# EDCPSUr9v0.net
KiCad netlist of a schematic drawn in EAGLE
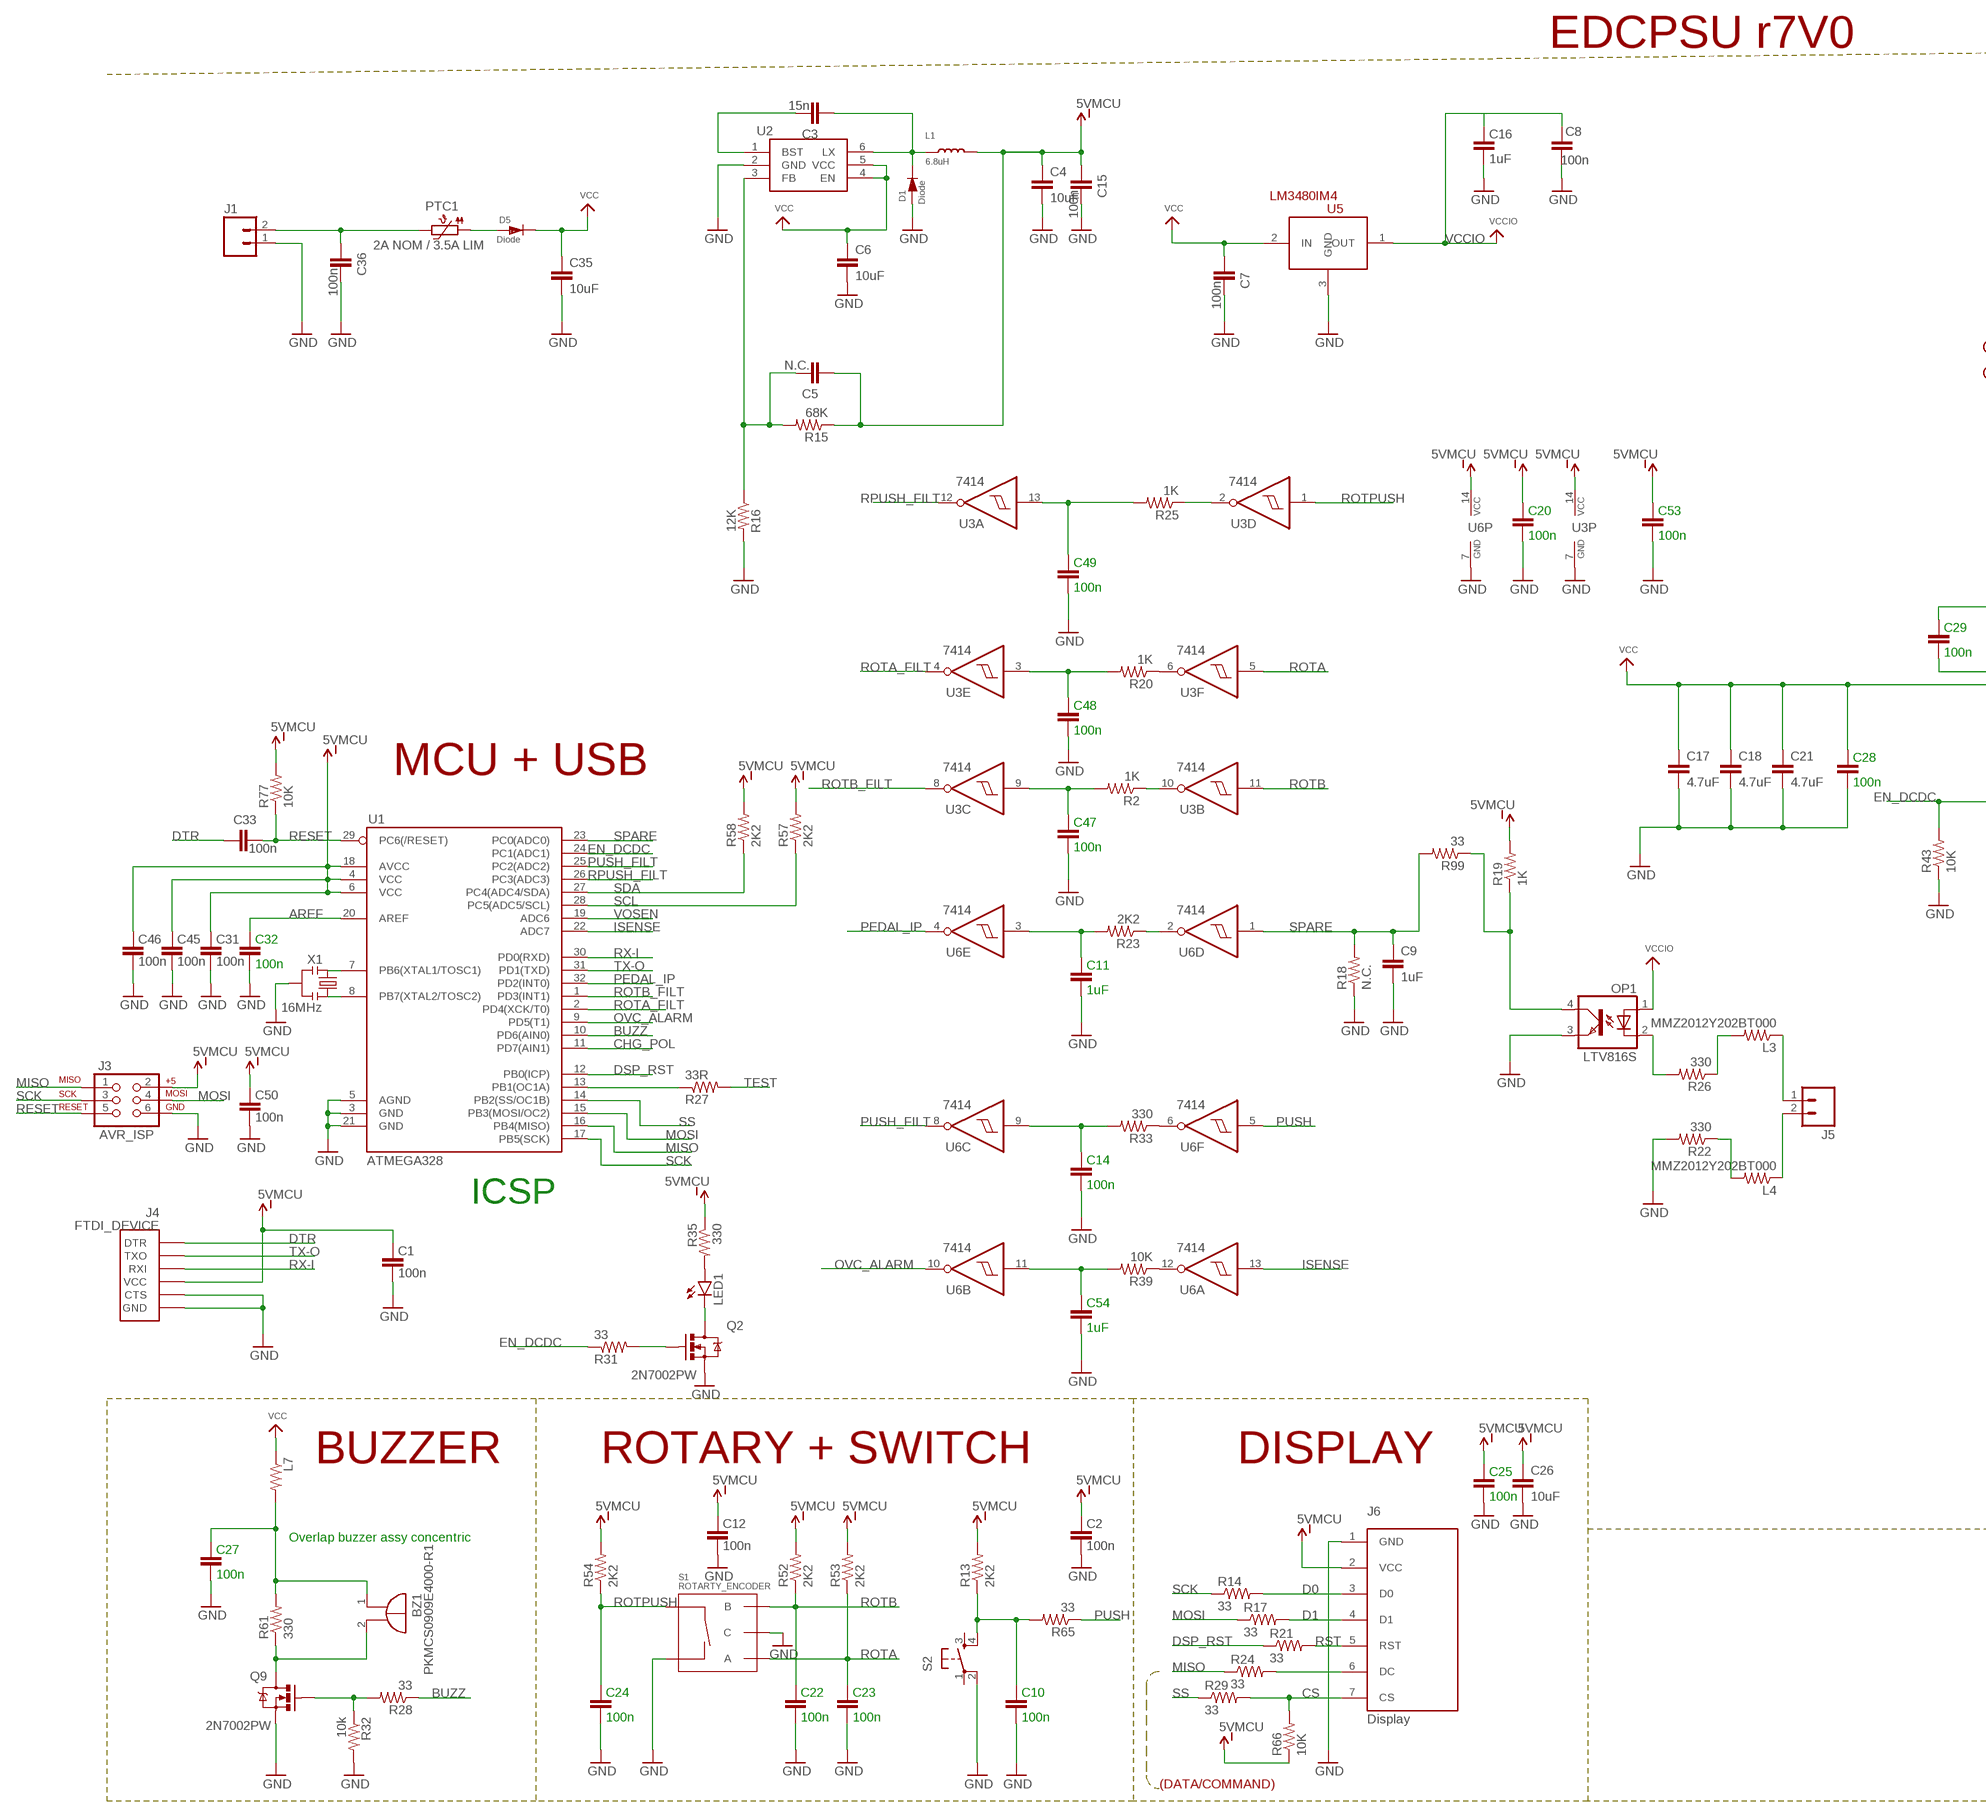
[diagram p0: schematic, sheet 1, part 1 of 2]
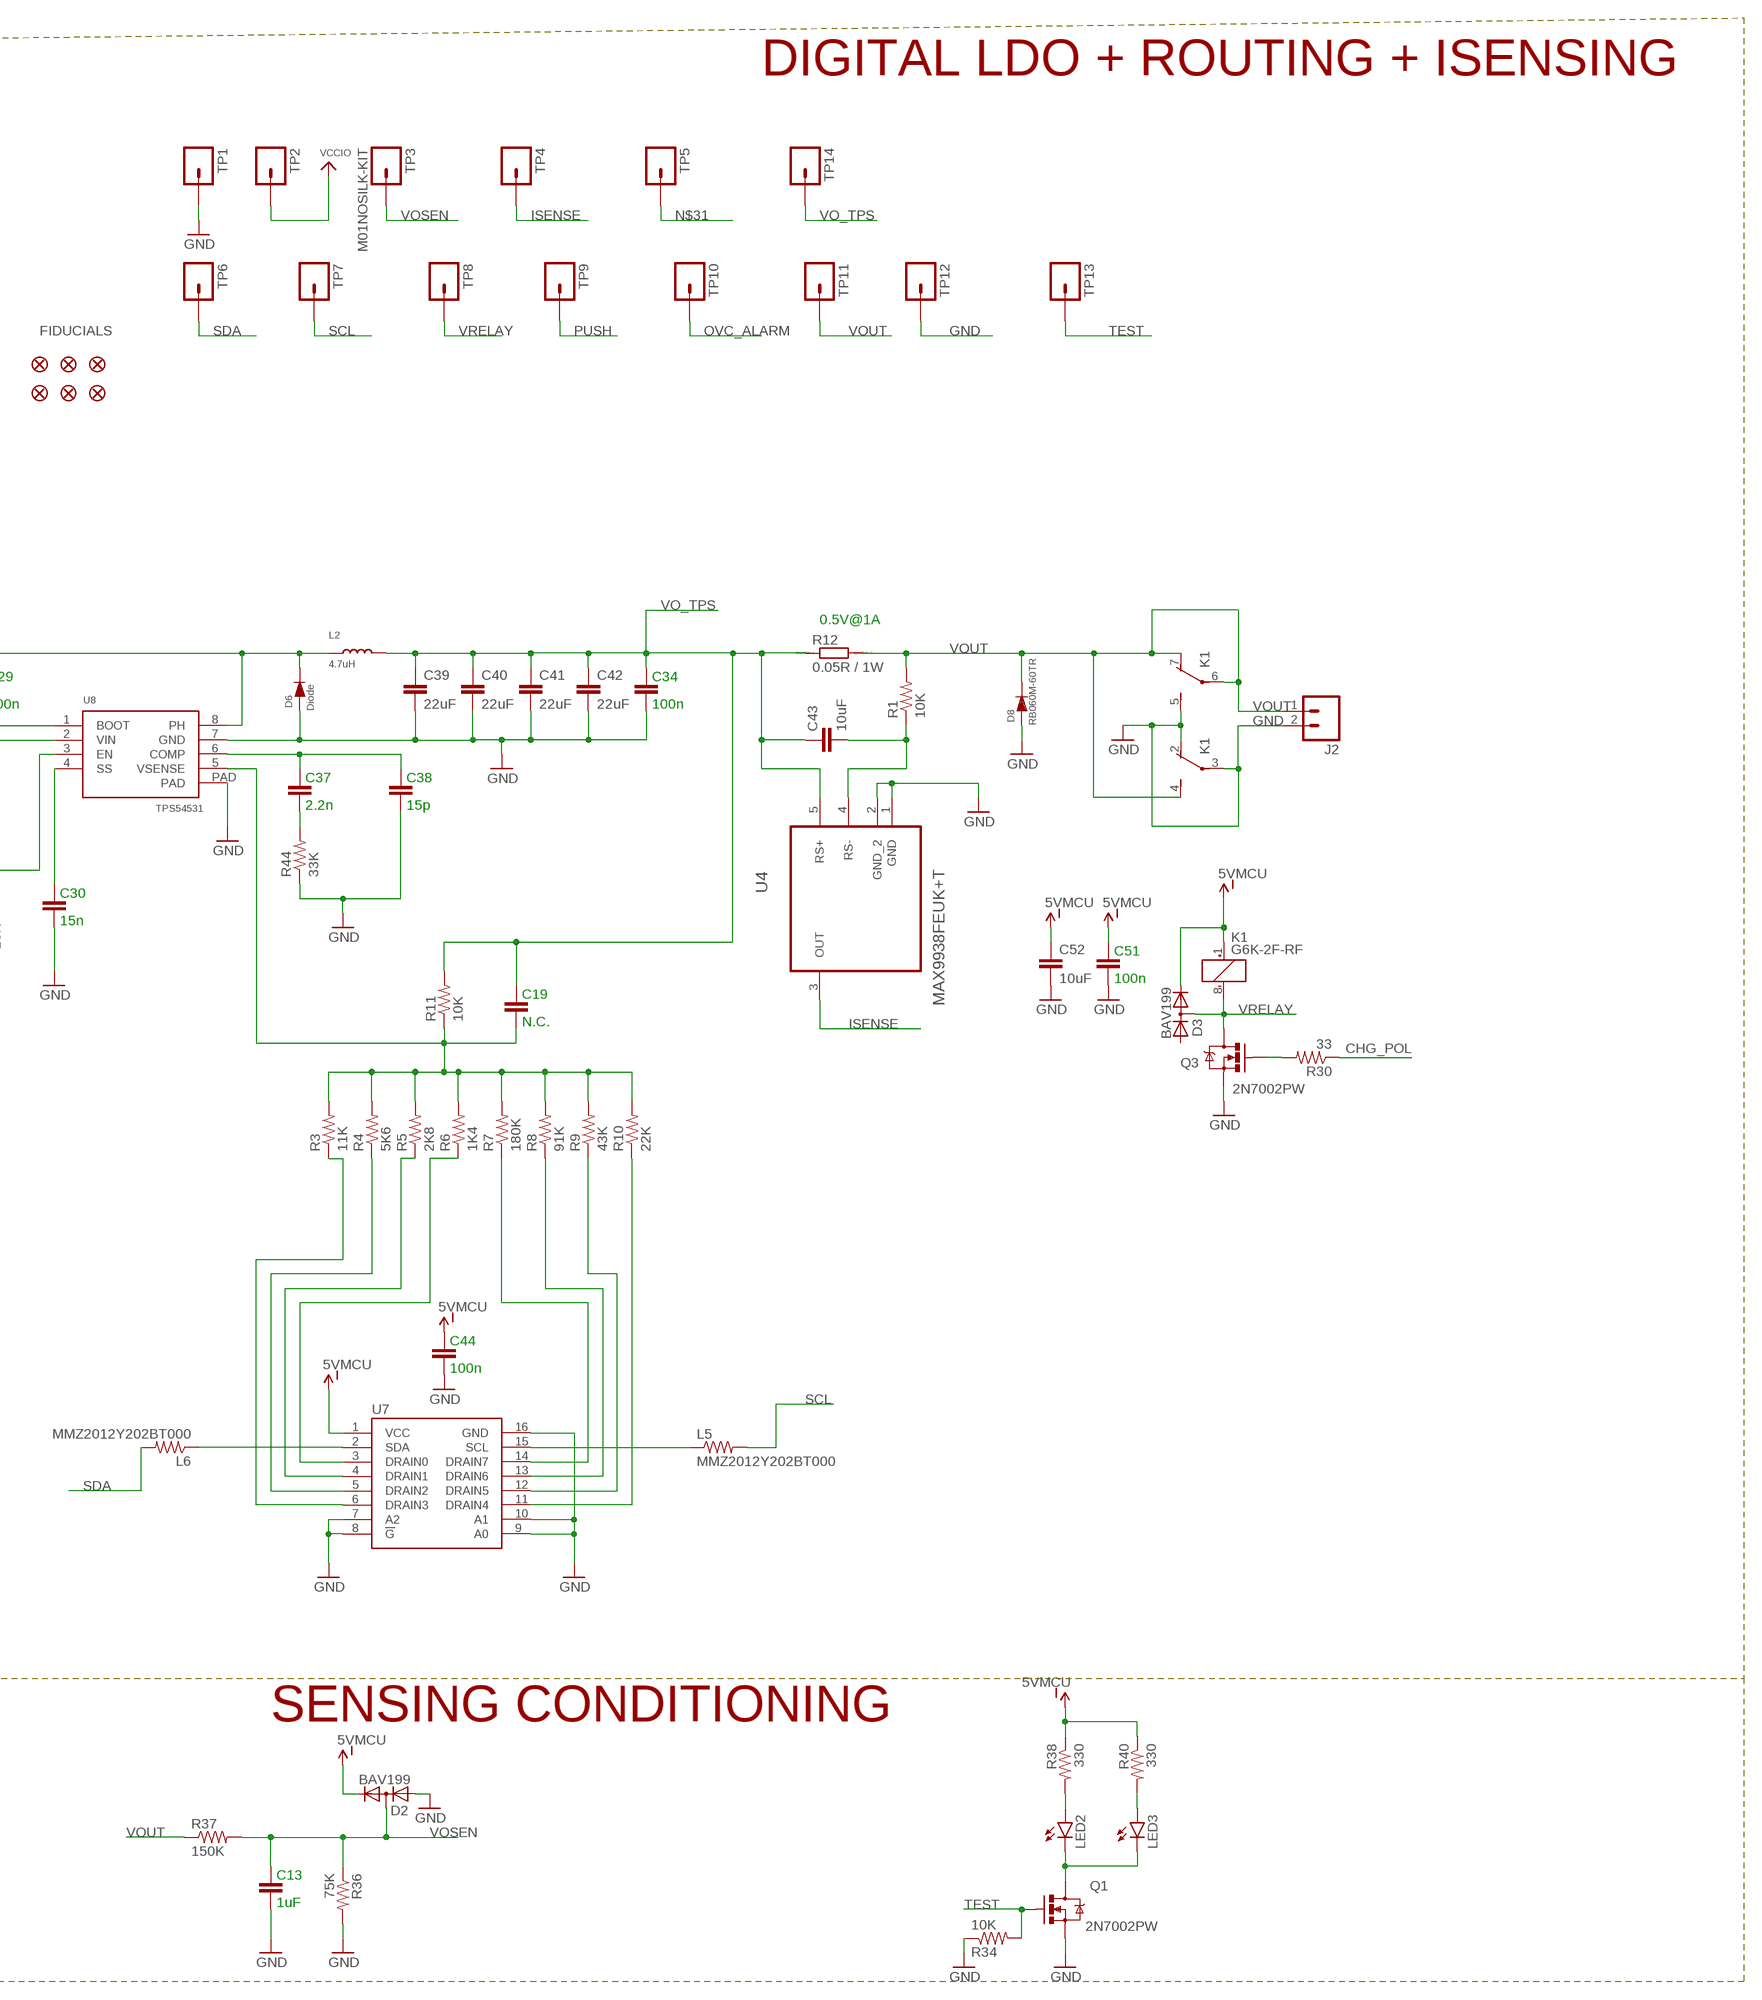
[diagram p1: schematic, sheet 1, part 2 of 2]

(export (version "E")
  (design (tool "Eeschema 10.0.6"))
  (components
    (comp (ref "BZ1")
      (value "PKMCS0909E4000-R1")
      (footprint "eagle-import:PKMCS0909")
      (libsource (lib "eagle-import") (part "PKMCS0909E4000-R1"))
    )
    (comp (ref "C1")
      (value "100n")
      (footprint "eagle-import:0805")
      (libsource (lib "eagle-import") (part "CAP0805"))
    )
    (comp (ref "C2")
      (value "100n")
      (footprint "eagle-import:0805")
      (libsource (lib "eagle-import") (part "CAP0805"))
    )
    (comp (ref "C3")
      (value "15n")
      (footprint "eagle-import:0805")
      (libsource (lib "eagle-import") (part "CAP0805"))
    )
    (comp (ref "C4")
      (value "10uF")
      (footprint "eagle-import:1206")
      (libsource (lib "eagle-import") (part "SparkFun-Passives_CAP1206"))
    )
    (comp (ref "C5")
      (value "N.C.")
      (footprint "eagle-import:0805")
      (libsource (lib "eagle-import") (part "CAP0805"))
    )
    (comp (ref "C6")
      (value "10uF")
      (footprint "eagle-import:1206")
      (libsource (lib "eagle-import") (part "SparkFun-Passives_CAP1206"))
    )
    (comp (ref "C7")
      (value "100n")
      (footprint "eagle-import:0805")
      (libsource (lib "eagle-import") (part "CAP0805"))
    )
    (comp (ref "C8")
      (value "100n")
      (footprint "eagle-import:0805")
      (libsource (lib "eagle-import") (part "CAP0805"))
    )
    (comp (ref "C9")
      (value "1uF")
      (footprint "eagle-import:1206")
      (libsource (lib "eagle-import") (part "SparkFun-Passives_CAP1206"))
    )
    (comp (ref "C10")
      (value "100n")
      (footprint "eagle-import:0805")
      (libsource (lib "eagle-import") (part "CAP0805"))
    )
    (comp (ref "C11")
      (value "1uF")
      (footprint "eagle-import:0805")
      (libsource (lib "eagle-import") (part "CAP0805"))
    )
    (comp (ref "C12")
      (value "100n")
      (footprint "eagle-import:0805")
      (libsource (lib "eagle-import") (part "CAP0805"))
    )
    (comp (ref "C13")
      (value "1uF")
      (footprint "eagle-import:0805")
      (libsource (lib "eagle-import") (part "CAP0805"))
    )
    (comp (ref "C14")
      (value "100n")
      (footprint "eagle-import:0805")
      (libsource (lib "eagle-import") (part "CAP0805"))
    )
    (comp (ref "C15")
      (value "100n")
      (footprint "eagle-import:0805")
      (libsource (lib "eagle-import") (part "CAP0805"))
    )
    (comp (ref "C16")
      (value "1uF")
      (footprint "eagle-import:0805")
      (libsource (lib "eagle-import") (part "CAP0805"))
    )
    (comp (ref "C17")
      (value "4.7uF")
      (footprint "eagle-import:1210")
      (libsource (lib "eagle-import") (part "SparkFun-Passives_CAP1210"))
    )
    (comp (ref "C18")
      (value "4.7uF")
      (footprint "eagle-import:1210")
      (libsource (lib "eagle-import") (part "SparkFun-Passives_CAP1210"))
    )
    (comp (ref "C19")
      (value "N.C.")
      (footprint "eagle-import:0805")
      (libsource (lib "eagle-import") (part "CAP0805"))
    )
    (comp (ref "C20")
      (value "100n")
      (footprint "eagle-import:0805")
      (libsource (lib "eagle-import") (part "CAP0805"))
    )
    (comp (ref "C21")
      (value "4.7uF")
      (footprint "eagle-import:1210")
      (libsource (lib "eagle-import") (part "SparkFun-Passives_CAP1210"))
    )
    (comp (ref "C22")
      (value "100n")
      (footprint "eagle-import:0805")
      (libsource (lib "eagle-import") (part "CAP0805"))
    )
    (comp (ref "C23")
      (value "100n")
      (footprint "eagle-import:0805")
      (libsource (lib "eagle-import") (part "CAP0805"))
    )
    (comp (ref "C24")
      (value "100n")
      (footprint "eagle-import:0805")
      (libsource (lib "eagle-import") (part "CAP0805"))
    )
    (comp (ref "C25")
      (value "100n")
      (footprint "eagle-import:0805")
      (libsource (lib "eagle-import") (part "CAP0805"))
    )
    (comp (ref "C26")
      (value "10uF")
      (footprint "eagle-import:1206")
      (libsource (lib "eagle-import") (part "SparkFun-Passives_CAP1206"))
    )
    (comp (ref "C27")
      (value "100n")
      (footprint "eagle-import:0805")
      (libsource (lib "eagle-import") (part "CAP0805"))
    )
    (comp (ref "C28")
      (value "100n")
      (footprint "eagle-import:0805")
      (libsource (lib "eagle-import") (part "CAP0805"))
    )
    (comp (ref "C29")
      (value "100n")
      (footprint "eagle-import:0805")
      (libsource (lib "eagle-import") (part "CAP0805"))
    )
    (comp (ref "C30")
      (value "15n")
      (footprint "eagle-import:0805")
      (libsource (lib "eagle-import") (part "CAP0805"))
    )
    (comp (ref "C31")
      (value "100n")
      (footprint "eagle-import:0805")
      (libsource (lib "eagle-import") (part "CAP0805"))
    )
    (comp (ref "C32")
      (value "100n")
      (footprint "eagle-import:0805")
      (libsource (lib "eagle-import") (part "CAP0805"))
    )
    (comp (ref "C33")
      (value "100n")
      (footprint "eagle-import:0805")
      (libsource (lib "eagle-import") (part "CAP0805"))
    )
    (comp (ref "C34")
      (value "100n")
      (footprint "eagle-import:0805")
      (libsource (lib "eagle-import") (part "CAP0805"))
    )
    (comp (ref "C35")
      (value "10uF")
      (footprint "eagle-import:1206")
      (libsource (lib "eagle-import") (part "SparkFun-Passives_CAP1206"))
    )
    (comp (ref "C36")
      (value "100n")
      (footprint "eagle-import:0805")
      (libsource (lib "eagle-import") (part "CAP0805"))
    )
    (comp (ref "C37")
      (value "2.2n")
      (footprint "eagle-import:0805")
      (libsource (lib "eagle-import") (part "CAP0805"))
    )
    (comp (ref "C38")
      (value "15p")
      (footprint "eagle-import:0805")
      (libsource (lib "eagle-import") (part "CAP0805"))
    )
    (comp (ref "C39")
      (value "22uF")
      (footprint "eagle-import:1210")
      (libsource (lib "eagle-import") (part "SparkFun-Passives_CAP1210"))
    )
    (comp (ref "C40")
      (value "22uF")
      (footprint "eagle-import:1210")
      (libsource (lib "eagle-import") (part "SparkFun-Passives_CAP1210"))
    )
    (comp (ref "C41")
      (value "22uF")
      (footprint "eagle-import:1210")
      (libsource (lib "eagle-import") (part "SparkFun-Passives_CAP1210"))
    )
    (comp (ref "C42")
      (value "22uF")
      (footprint "eagle-import:1210")
      (libsource (lib "eagle-import") (part "SparkFun-Passives_CAP1210"))
    )
    (comp (ref "C43")
      (value "10uF")
      (footprint "eagle-import:1206")
      (libsource (lib "eagle-import") (part "SparkFun-Passives_CAP1206"))
    )
    (comp (ref "C44")
      (value "100n")
      (footprint "eagle-import:0805")
      (libsource (lib "eagle-import") (part "CAP0805"))
    )
    (comp (ref "C45")
      (value "100n")
      (footprint "eagle-import:0805")
      (libsource (lib "eagle-import") (part "CAP0805"))
    )
    (comp (ref "C46")
      (value "100n")
      (footprint "eagle-import:0805")
      (libsource (lib "eagle-import") (part "CAP0805"))
    )
    (comp (ref "C47")
      (value "100n")
      (footprint "eagle-import:0805")
      (libsource (lib "eagle-import") (part "CAP0805"))
    )
    (comp (ref "C48")
      (value "100n")
      (footprint "eagle-import:0805")
      (libsource (lib "eagle-import") (part "CAP0805"))
    )
    (comp (ref "C49")
      (value "100n")
      (footprint "eagle-import:0805")
      (libsource (lib "eagle-import") (part "CAP0805"))
    )
    (comp (ref "C50")
      (value "100n")
      (footprint "eagle-import:0805")
      (libsource (lib "eagle-import") (part "CAP0805"))
    )
    (comp (ref "C51")
      (value "100n")
      (footprint "eagle-import:0805")
      (libsource (lib "eagle-import") (part "CAP0805"))
    )
    (comp (ref "C52")
      (value "10uF")
      (footprint "eagle-import:1206")
      (libsource (lib "eagle-import") (part "SparkFun-Passives_CAP1206"))
    )
    (comp (ref "C53")
      (value "100n")
      (footprint "eagle-import:0805")
      (libsource (lib "eagle-import") (part "CAP0805"))
    )
    (comp (ref "C54")
      (value "1uF")
      (footprint "eagle-import:0805")
      (libsource (lib "eagle-import") (part "CAP0805"))
    )
    (comp (ref "D1")
      (value "Diode")
      (footprint "eagle-import:SOD123")
      (libsource (lib "eagle-import") (part "DSOD123"))
    )
    (comp (ref "D2")
      (value "BAV199")
      (footprint "eagle-import:SOT23")
      (libsource (lib "eagle-import") (part "BAV199"))
    )
    (comp (ref "D3")
      (value "BAV199")
      (footprint "eagle-import:SOT23")
      (libsource (lib "eagle-import") (part "BAV199"))
    )
    (comp (ref "D5")
      (value "Diode")
      (footprint "eagle-import:DO-214AB")
      (libsource (lib "eagle-import") (part "DSMC"))
    )
    (comp (ref "D6")
      (value "Diode")
      (footprint "eagle-import:DO-214AB")
      (libsource (lib "eagle-import") (part "DSMC"))
    )
    (comp (ref "D8")
      (value "RB060M-60TR")
      (footprint "eagle-import:SMADIODE")
      (libsource (lib "eagle-import") (part "DSMA"))
    )
    (comp (ref "FID1")
      (value "FIDUCIAL1X2")
      (footprint "eagle-import:FIDUCIAL-1X2")
      (libsource (lib "eagle-import") (part "FIDUCIAL1X2"))
    )
    (comp (ref "FID2")
      (value "FIDUCIAL1X2")
      (footprint "eagle-import:FIDUCIAL-1X2")
      (libsource (lib "eagle-import") (part "FIDUCIAL1X2"))
    )
    (comp (ref "FID3")
      (value "FIDUCIAL1X2")
      (footprint "eagle-import:FIDUCIAL-1X2")
      (libsource (lib "eagle-import") (part "FIDUCIAL1X2"))
    )
    (comp (ref "FID4")
      (value "FIDUCIAL1X2")
      (footprint "eagle-import:FIDUCIAL-1X2")
      (libsource (lib "eagle-import") (part "FIDUCIAL1X2"))
    )
    (comp (ref "FID5")
      (value "FIDUCIAL1X2")
      (footprint "eagle-import:FIDUCIAL-1X2")
      (libsource (lib "eagle-import") (part "FIDUCIAL1X2"))
    )
    (comp (ref "FID6")
      (value "FIDUCIAL1X2")
      (footprint "eagle-import:FIDUCIAL-1X2")
      (libsource (lib "eagle-import") (part "FIDUCIAL1X2"))
    )
    (comp (ref "J1")
      (value "M02LOCK_LONGPADS")
      (footprint "eagle-import:1X02_LOCK_LONGPADS")
      (libsource (lib "eagle-import") (part "M02LOCK_LONGPADS"))
    )
    (comp (ref "J2")
      (value "M02LOCK_LONGPADS")
      (footprint "eagle-import:1X02_LOCK_LONGPADS")
      (libsource (lib "eagle-import") (part "M02LOCK_LONGPADS"))
    )
    (comp (ref "J3")
      (value "AVR_ISP")
      (footprint "eagle-import:2X3")
      (libsource (lib "eagle-import") (part "AVR_SPI_PRG_6PTH"))
    )
    (comp (ref "J4")
      (value "FTDI_DEVICE")
      (footprint "eagle-import:FTDI_DEVICE_SIDE")
      (libsource (lib "eagle-import") (part "FTDI_DEVICE"))
    )
    (comp (ref "J5")
      (value "M02LOCK_LONGPADS")
      (footprint "eagle-import:1X02_LOCK_LONGPADS")
      (libsource (lib "eagle-import") (part "M02LOCK_LONGPADS"))
    )
    (comp (ref "J6")
      (value "Display")
      (footprint "eagle-import:OLED_LCD")
      (libsource (lib "eagle-import") (part "OLED_LCD"))
    )
    (comp (ref "K1")
      (value "G6K-2F-RF")
      (footprint "eagle-import:G6K-RF")
      (fields (field (name "MF") "OMRON COMPONENTS USA") (field (name "MPN") "G6K-2F-RF-DC12"))
      (libsource (lib "eagle-import") (part "G6K-2F-RF"))
    )
    (comp (ref "L1")
      (value "6.8uH")
      (footprint "eagle-import:NR4018T100M")
      (libsource (lib "eagle-import") (part "L4018"))
    )
    (comp (ref "L2")
      (value "4.7uH")
      (footprint "eagle-import:WE-LHMI")
      (libsource (lib "eagle-import") (part "L74437368047"))
    )
    (comp (ref "L3")
      (value "MMZ2012Y202BT000")
      (footprint "eagle-import:0805")
      (libsource (lib "eagle-import") (part "RESISTOR0805-RES"))
    )
    (comp (ref "L4")
      (value "MMZ2012Y202BT000")
      (footprint "eagle-import:0805")
      (libsource (lib "eagle-import") (part "RESISTOR0805-RES"))
    )
    (comp (ref "L5")
      (value "MMZ2012Y202BT000")
      (footprint "eagle-import:0805")
      (libsource (lib "eagle-import") (part "RESISTOR0805-RES"))
    )
    (comp (ref "L6")
      (value "MMZ2012Y202BT000")
      (footprint "eagle-import:0805")
      (libsource (lib "eagle-import") (part "RESISTOR0805-RES"))
    )
    (comp (ref "L7")
      (value "MMZ2012Y202BT000")
      (footprint "eagle-import:0805")
      (libsource (lib "eagle-import") (part "RESISTOR0805-RES"))
    )
    (comp (ref "LED1")
      (value "LED3MM")
      (footprint "eagle-import:LED3MM")
      (libsource (lib "eagle-import") (part "LED3MM"))
    )
    (comp (ref "LED2")
      (value "LED5MM")
      (footprint "eagle-import:LED5MM")
      (libsource (lib "eagle-import") (part "LED5MM"))
    )
    (comp (ref "LED3")
      (value "LED5MM")
      (footprint "eagle-import:LED5MM")
      (libsource (lib "eagle-import") (part "LED5MM"))
    )
    (comp (ref "OP1")
      (value "LTV816S")
      (footprint "eagle-import:SMD4")
      (libsource (lib "eagle-import") (part "LTV816S"))
    )
    (comp (ref "PTC1")
      (value "2A NOM / 3.5A LIM")
      (footprint "eagle-import:1812L")
      (libsource (lib "eagle-import") (part "PTC-"))
    )
    (comp (ref "Q1")
      (value "2N7002PW")
      (footprint "eagle-import:SOT323")
      (libsource (lib "eagle-import") (part "MOSFET-NCHANNEL2N7002PW"))
    )
    (comp (ref "Q2")
      (value "2N7002PW")
      (footprint "eagle-import:SOT323")
      (libsource (lib "eagle-import") (part "MOSFET-NCHANNEL2N7002PW"))
    )
    (comp (ref "Q3")
      (value "2N7002PW")
      (footprint "eagle-import:SOT323")
      (libsource (lib "eagle-import") (part "MOSFET-NCHANNEL2N7002PW"))
    )
    (comp (ref "Q9")
      (value "2N7002PW")
      (footprint "eagle-import:SOT323")
      (libsource (lib "eagle-import") (part "MOSFET-NCHANNEL2N7002PW"))
    )
    (comp (ref "R1")
      (value "10K")
      (footprint "eagle-import:0805")
      (libsource (lib "eagle-import") (part "RESISTOR0805-RES"))
    )
    (comp (ref "R2")
      (value "1K")
      (footprint "eagle-import:0805")
      (libsource (lib "eagle-import") (part "RESISTOR0805-RES"))
    )
    (comp (ref "R3")
      (value "11K")
      (footprint "eagle-import:0805")
      (libsource (lib "eagle-import") (part "RESISTOR0805-RES"))
    )
    (comp (ref "R4")
      (value "5K6")
      (footprint "eagle-import:0805")
      (libsource (lib "eagle-import") (part "RESISTOR0805-RES"))
    )
    (comp (ref "R5")
      (value "2K8")
      (footprint "eagle-import:0805")
      (libsource (lib "eagle-import") (part "RESISTOR0805-RES"))
    )
    (comp (ref "R6")
      (value "1K4")
      (footprint "eagle-import:0805")
      (libsource (lib "eagle-import") (part "RESISTOR0805-RES"))
    )
    (comp (ref "R7")
      (value "180K")
      (footprint "eagle-import:0805")
      (libsource (lib "eagle-import") (part "RESISTOR0805-RES"))
    )
    (comp (ref "R8")
      (value "91K")
      (footprint "eagle-import:0805")
      (libsource (lib "eagle-import") (part "RESISTOR0805-RES"))
    )
    (comp (ref "R9")
      (value "43K")
      (footprint "eagle-import:0805")
      (libsource (lib "eagle-import") (part "RESISTOR0805-RES"))
    )
    (comp (ref "R10")
      (value "22K")
      (footprint "eagle-import:0805")
      (libsource (lib "eagle-import") (part "RESISTOR0805-RES"))
    )
    (comp (ref "R11")
      (value "10K")
      (footprint "eagle-import:0805")
      (libsource (lib "eagle-import") (part "RESISTOR0805-RES"))
    )
    (comp (ref "R12")
      (value "0.05R / 1W")
      (footprint "eagle-import:R2512")
      (libsource (lib "eagle-import") (part "RR2512"))
    )
    (comp (ref "R13")
      (value "2K2")
      (footprint "eagle-import:0805")
      (libsource (lib "eagle-import") (part "RESISTOR0805-RES"))
    )
    (comp (ref "R14")
      (value "33")
      (footprint "eagle-import:0805")
      (libsource (lib "eagle-import") (part "RESISTOR0805-RES"))
    )
    (comp (ref "R15")
      (value "68K")
      (footprint "eagle-import:0805")
      (libsource (lib "eagle-import") (part "RESISTOR0805-RES"))
    )
    (comp (ref "R16")
      (value "12K")
      (footprint "eagle-import:0805")
      (libsource (lib "eagle-import") (part "RESISTOR0805-RES"))
    )
    (comp (ref "R17")
      (value "33")
      (footprint "eagle-import:0805")
      (libsource (lib "eagle-import") (part "RESISTOR0805-RES"))
    )
    (comp (ref "R18")
      (value "N.C.")
      (footprint "eagle-import:0805")
      (libsource (lib "eagle-import") (part "RESISTOR0805-RES"))
    )
    (comp (ref "R19")
      (value "1K")
      (footprint "eagle-import:0805")
      (libsource (lib "eagle-import") (part "RESISTOR0805-RES"))
    )
    (comp (ref "R20")
      (value "1K")
      (footprint "eagle-import:0805")
      (libsource (lib "eagle-import") (part "RESISTOR0805-RES"))
    )
    (comp (ref "R21")
      (value "33")
      (footprint "eagle-import:0805")
      (libsource (lib "eagle-import") (part "RESISTOR0805-RES"))
    )
    (comp (ref "R22")
      (value "330")
      (footprint "eagle-import:1206")
      (libsource (lib "eagle-import") (part "SparkFun-Passives_RESISTOR1206"))
    )
    (comp (ref "R23")
      (value "2K2")
      (footprint "eagle-import:0805")
      (libsource (lib "eagle-import") (part "RESISTOR0805-RES"))
    )
    (comp (ref "R24")
      (value "33")
      (footprint "eagle-import:0805")
      (libsource (lib "eagle-import") (part "RESISTOR0805-RES"))
    )
    (comp (ref "R25")
      (value "1K")
      (footprint "eagle-import:0805")
      (libsource (lib "eagle-import") (part "RESISTOR0805-RES"))
    )
    (comp (ref "R26")
      (value "330")
      (footprint "eagle-import:1206")
      (libsource (lib "eagle-import") (part "SparkFun-Passives_RESISTOR1206"))
    )
    (comp (ref "R27")
      (value "33R")
      (footprint "eagle-import:0805")
      (libsource (lib "eagle-import") (part "RESISTOR0805-RES"))
    )
    (comp (ref "R28")
      (value "33")
      (footprint "eagle-import:0805")
      (libsource (lib "eagle-import") (part "RESISTOR0805-RES"))
    )
    (comp (ref "R29")
      (value "33")
      (footprint "eagle-import:0805")
      (libsource (lib "eagle-import") (part "RESISTOR0805-RES"))
    )
    (comp (ref "R30")
      (value "33")
      (footprint "eagle-import:0805")
      (libsource (lib "eagle-import") (part "RESISTOR0805-RES"))
    )
    (comp (ref "R31")
      (value "33")
      (footprint "eagle-import:0805")
      (libsource (lib "eagle-import") (part "RESISTOR0805-RES"))
    )
    (comp (ref "R32")
      (value "10k")
      (footprint "eagle-import:0805")
      (libsource (lib "eagle-import") (part "RESISTOR0805-RES"))
    )
    (comp (ref "R33")
      (value "330")
      (footprint "eagle-import:0805")
      (libsource (lib "eagle-import") (part "RESISTOR0805-RES"))
    )
    (comp (ref "R34")
      (value "10K")
      (footprint "eagle-import:0805")
      (libsource (lib "eagle-import") (part "RESISTOR0805-RES"))
    )
    (comp (ref "R35")
      (value "330")
      (footprint "eagle-import:0805")
      (libsource (lib "eagle-import") (part "RESISTOR0805-RES"))
    )
    (comp (ref "R36")
      (value "75K")
      (footprint "eagle-import:0805")
      (libsource (lib "eagle-import") (part "RESISTOR0805-RES"))
    )
    (comp (ref "R37")
      (value "150K")
      (footprint "eagle-import:0805")
      (libsource (lib "eagle-import") (part "RESISTOR0805-RES"))
    )
    (comp (ref "R38")
      (value "330")
      (footprint "eagle-import:0805")
      (libsource (lib "eagle-import") (part "RESISTOR0805-RES"))
    )
    (comp (ref "R39")
      (value "10K")
      (footprint "eagle-import:0805")
      (libsource (lib "eagle-import") (part "RESISTOR0805-RES"))
    )
    (comp (ref "R40")
      (value "330")
      (footprint "eagle-import:0805")
      (libsource (lib "eagle-import") (part "RESISTOR0805-RES"))
    )
    (comp (ref "R43")
      (value "10K")
      (footprint "eagle-import:0805")
      (libsource (lib "eagle-import") (part "RESISTOR0805-RES"))
    )
    (comp (ref "R44")
      (value "33K")
      (footprint "eagle-import:0805")
      (libsource (lib "eagle-import") (part "RESISTOR0805-RES"))
    )
    (comp (ref "R52")
      (value "2K2")
      (footprint "eagle-import:0805")
      (libsource (lib "eagle-import") (part "RESISTOR0805-RES"))
    )
    (comp (ref "R53")
      (value "2K2")
      (footprint "eagle-import:0805")
      (libsource (lib "eagle-import") (part "RESISTOR0805-RES"))
    )
    (comp (ref "R54")
      (value "2K2")
      (footprint "eagle-import:0805")
      (libsource (lib "eagle-import") (part "RESISTOR0805-RES"))
    )
    (comp (ref "R57")
      (value "2K2")
      (footprint "eagle-import:0805")
      (libsource (lib "eagle-import") (part "RESISTOR0805-RES"))
    )
    (comp (ref "R58")
      (value "2K2")
      (footprint "eagle-import:0805")
      (libsource (lib "eagle-import") (part "RESISTOR0805-RES"))
    )
    (comp (ref "R61")
      (value "330")
      (footprint "eagle-import:0805")
      (libsource (lib "eagle-import") (part "RESISTOR0805-RES"))
    )
    (comp (ref "R65")
      (value "33")
      (footprint "eagle-import:0805")
      (libsource (lib "eagle-import") (part "RESISTOR0805-RES"))
    )
    (comp (ref "R66")
      (value "10K")
      (footprint "eagle-import:0805")
      (libsource (lib "eagle-import") (part "RESISTOR0805-RES"))
    )
    (comp (ref "R77")
      (value "10K")
      (footprint "eagle-import:0805")
      (libsource (lib "eagle-import") (part "RESISTOR0805-RES"))
    )
    (comp (ref "R99")
      (value "33")
      (footprint "eagle-import:0805")
      (libsource (lib "eagle-import") (part "RESISTOR0805-RES"))
    )
    (comp (ref "S1")
      (value "ROTARTY_ENCODER")
      (footprint "eagle-import:ROTARY_ENC_PLAIN")
      (libsource (lib "eagle-import") (part "ROTARTY_ENCODER"))
    )
    (comp (ref "S2")
      (value "TAC_SWITCH_KSC931G-SMD")
      (footprint "eagle-import:TAC_SW_SMD_KSC931G")
      (libsource (lib "eagle-import") (part "TAC_SWITCH_KSC931G-SMD"))
    )
    (comp (ref "TP1")
      (value "M01POGOPIN_HOLE_LARGE")
      (footprint "eagle-import:1X01_POGOPIN_HOLE_LARGE")
      (libsource (lib "eagle-import") (part "M01POGOPIN_HOLE_LARGE"))
    )
    (comp (ref "TP2")
      (value "M01POGOPIN_HOLE_LARGE")
      (footprint "eagle-import:1X01_POGOPIN_HOLE_LARGE")
      (libsource (lib "eagle-import") (part "M01POGOPIN_HOLE_LARGE"))
    )
    (comp (ref "TP3")
      (value "M01NOSILK-KIT")
      (footprint "eagle-import:1X01NS-KIT")
      (libsource (lib "eagle-import") (part "M01NOSILK-KIT"))
    )
    (comp (ref "TP4")
      (value "M01POGOPIN_HOLE_LARGE")
      (footprint "eagle-import:1X01_POGOPIN_HOLE_LARGE")
      (libsource (lib "eagle-import") (part "M01POGOPIN_HOLE_LARGE"))
    )
    (comp (ref "TP5")
      (value "M01POGOPIN_HOLE_LARGE")
      (footprint "eagle-import:1X01_POGOPIN_HOLE_LARGE")
      (libsource (lib "eagle-import") (part "M01POGOPIN_HOLE_LARGE"))
    )
    (comp (ref "TP6")
      (value "M01POGOPIN_HOLE_LARGE")
      (footprint "eagle-import:1X01_POGOPIN_HOLE_LARGE")
      (libsource (lib "eagle-import") (part "M01POGOPIN_HOLE_LARGE"))
    )
    (comp (ref "TP7")
      (value "M01POGOPIN_HOLE_LARGE")
      (footprint "eagle-import:1X01_POGOPIN_HOLE_LARGE")
      (libsource (lib "eagle-import") (part "M01POGOPIN_HOLE_LARGE"))
    )
    (comp (ref "TP8")
      (value "M01POGOPIN_HOLE_LARGE")
      (footprint "eagle-import:1X01_POGOPIN_HOLE_LARGE")
      (libsource (lib "eagle-import") (part "M01POGOPIN_HOLE_LARGE"))
    )
    (comp (ref "TP9")
      (value "M01POGOPIN_HOLE_LARGE")
      (footprint "eagle-import:1X01_POGOPIN_HOLE_LARGE")
      (libsource (lib "eagle-import") (part "M01POGOPIN_HOLE_LARGE"))
    )
    (comp (ref "TP10")
      (value "M01POGOPIN_HOLE_LARGE")
      (footprint "eagle-import:1X01_POGOPIN_HOLE_LARGE")
      (libsource (lib "eagle-import") (part "M01POGOPIN_HOLE_LARGE"))
    )
    (comp (ref "TP11")
      (value "M01POGOPIN_HOLE_LARGE")
      (footprint "eagle-import:1X01_POGOPIN_HOLE_LARGE")
      (libsource (lib "eagle-import") (part "M01POGOPIN_HOLE_LARGE"))
    )
    (comp (ref "TP12")
      (value "M01POGOPIN_HOLE_LARGE")
      (footprint "eagle-import:1X01_POGOPIN_HOLE_LARGE")
      (libsource (lib "eagle-import") (part "M01POGOPIN_HOLE_LARGE"))
    )
    (comp (ref "TP13")
      (value "M01POGOPIN_HOLE_LARGE")
      (footprint "eagle-import:1X01_POGOPIN_HOLE_LARGE")
      (libsource (lib "eagle-import") (part "M01POGOPIN_HOLE_LARGE"))
    )
    (comp (ref "TP14")
      (value "M01POGOPIN_HOLE_LARGE")
      (footprint "eagle-import:1X01_POGOPIN_HOLE_LARGE")
      (libsource (lib "eagle-import") (part "M01POGOPIN_HOLE_LARGE"))
    )
    (comp (ref "U1")
      (value "ATMEGA328")
      (footprint "eagle-import:TQFP32-08")
      (libsource (lib "eagle-import") (part "ATMEGA168"))
    )
    (comp (ref "U2")
      (value "BD9G101G")
      (footprint "eagle-import:SSOP6")
      (libsource (lib "eagle-import") (part "BD9G101G"))
    )
    (comp (ref "U3")
      (value "7414")
      (footprint "eagle-import:TSSOP14")
      (libsource (lib "eagle-import") (part "7414"))
    )
    (comp (ref "U4")
      (value "MAX9938FEUK+T")
      (footprint "eagle-import:SOT95P280X145-5N")
      (libsource (lib "eagle-import") (part "MAX9938FEUK+T"))
    )
    (comp (ref "U5")
      (value "LM3480IM4")
      (footprint "eagle-import:SOT23-3")
      (libsource (lib "eagle-import") (part "LM3480IM4"))
    )
    (comp (ref "U6")
      (value "7414")
      (footprint "eagle-import:TSSOP14")
      (libsource (lib "eagle-import") (part "7414"))
    )
    (comp (ref "U7")
      (value "TPIC2810D")
      (footprint "eagle-import:SO16")
      (libsource (lib "eagle-import") (part "TPIC2810D"))
    )
    (comp (ref "U8")
      (value "TPS54531")
      (footprint "eagle-import:SOIC8")
      (libsource (lib "eagle-import") (part "TPS5431DDAR"))
    )
    (comp (ref "X1")
      (value "16MHz")
      (footprint "eagle-import:RESONATOR-SMD")
      (libsource (lib "eagle-import") (part "RESONATORSMD"))
    )
  )
  (nets
    (net (code "1") (name "/AREF") (class "Default")
      (node (ref "C32") (pin "2") (pinfunction "2_2") (pintype "passive"))
      (node (ref "U1") (pin "20") (pinfunction "AREF_20") (pintype "bidirectional"))
    )
    (net (code "2") (name "/BUZZ") (class "Default")
      (node (ref "R28") (pin "1") (pinfunction "1_1") (pintype "passive"))
      (node (ref "U1") (pin "10") (pinfunction "PD6(AIN0)_10") (pintype "bidirectional"))
    )
    (net (code "3") (name "/CHG_POL") (class "Default")
      (node (ref "R30") (pin "1") (pinfunction "1_1") (pintype "passive"))
      (node (ref "U1") (pin "11") (pinfunction "PD7(AIN1)_11") (pintype "bidirectional"))
    )
    (net (code "4") (name "/CS") (class "Default")
      (node (ref "J6") (pin "7") (pinfunction "CS_7") (pintype "bidirectional"))
      (node (ref "R29") (pin "2") (pinfunction "2_2") (pintype "passive"))
      (node (ref "R66") (pin "2") (pinfunction "2_2") (pintype "passive"))
    )
    (net (code "5") (name "/D0") (class "Default")
      (node (ref "J6") (pin "3") (pinfunction "D0_3") (pintype "bidirectional"))
      (node (ref "R14") (pin "2") (pinfunction "2_2") (pintype "passive"))
    )
    (net (code "6") (name "/D1") (class "Default")
      (node (ref "J6") (pin "4") (pinfunction "D1_4") (pintype "bidirectional"))
      (node (ref "R17") (pin "2") (pinfunction "2_2") (pintype "passive"))
    )
    (net (code "7") (name "/DSP_RST") (class "Default")
      (node (ref "R21") (pin "1") (pinfunction "1_1") (pintype "passive"))
      (node (ref "U1") (pin "12") (pinfunction "PB0(ICP)_12") (pintype "bidirectional"))
    )
    (net (code "8") (name "/DTR") (class "Default")
      (node (ref "C33") (pin "2") (pinfunction "2_2") (pintype "passive"))
      (node (ref "J4") (pin "P$1") (pinfunction "DTR_P$1") (pintype "bidirectional"))
    )
    (net (code "9") (name "/EN_DCDC") (class "Default")
      (node (ref "R31") (pin "1") (pinfunction "1_1") (pintype "passive"))
      (node (ref "R43") (pin "2") (pinfunction "2_2") (pintype "passive"))
      (node (ref "U1") (pin "24") (pinfunction "PC1(ADC1)_24") (pintype "bidirectional"))
      (node (ref "U8") (pin "3") (pinfunction "EN_3") (pintype "bidirectional"))
    )
    (net (code "10") (name "/ISENSE") (class "Default")
      (node (ref "TP4") (pin "1") (pinfunction "1_1") (pintype "passive"))
      (node (ref "U1") (pin "22") (pinfunction "ADC7_22") (pintype "bidirectional"))
      (node (ref "U4") (pin "3") (pinfunction "OUT_3") (pintype "output"))
      (node (ref "U6") (pin "13") (pinfunction "I_13") (pintype "input"))
    )
    (net (code "11") (name "/MISO") (class "Default")
      (node (ref "J3") (pin "1") (pinfunction "1_1") (pintype "passive"))
      (node (ref "R24") (pin "1") (pinfunction "1_1") (pintype "passive"))
      (node (ref "U1") (pin "16") (pinfunction "PB4(MISO)_16") (pintype "bidirectional"))
    )
    (net (code "12") (name "/MOSI") (class "Default")
      (node (ref "J3") (pin "4") (pinfunction "4_4") (pintype "passive"))
      (node (ref "R17") (pin "1") (pinfunction "1_1") (pintype "passive"))
      (node (ref "U1") (pin "15") (pinfunction "PB3(MOSI/OC2)_15") (pintype "bidirectional"))
    )
    (net (code "13") (name "/N$31") (class "Default")
      (node (ref "OP1") (pin "4") (pinfunction "COL_4") (pintype "passive"))
      (node (ref "R19") (pin "1") (pinfunction "1_1") (pintype "passive"))
      (node (ref "R99") (pin "1") (pinfunction "1_1") (pintype "passive"))
      (node (ref "TP5") (pin "1") (pinfunction "1_1") (pintype "passive"))
    )
    (net (code "14") (name "/OVC_ALARM") (class "Default")
      (node (ref "TP10") (pin "1") (pinfunction "1_1") (pintype "passive"))
      (node (ref "U1") (pin "9") (pinfunction "PD5(T1)_9") (pintype "bidirectional"))
      (node (ref "U6") (pin "10") (pinfunction "O_10") (pintype "output"))
    )
    (net (code "15") (name "/PEDAL_IP") (class "Default")
      (node (ref "U1") (pin "32") (pinfunction "PD2(INT0)_32") (pintype "bidirectional"))
      (node (ref "U6") (pin "4") (pinfunction "O_4") (pintype "output"))
    )
    (net (code "16") (name "/PUSH") (class "Default")
      (node (ref "R65") (pin "1") (pinfunction "1_1") (pintype "passive"))
      (node (ref "TP9") (pin "1") (pinfunction "1_1") (pintype "passive"))
      (node (ref "U6") (pin "5") (pinfunction "I_5") (pintype "input"))
    )
    (net (code "17") (name "/PUSH_FILT") (class "Default")
      (node (ref "U1") (pin "25") (pinfunction "PC2(ADC2)_25") (pintype "bidirectional"))
      (node (ref "U6") (pin "8") (pinfunction "O_8") (pintype "output"))
    )
    (net (code "18") (name "/RESET") (class "Default")
      (node (ref "C33") (pin "1") (pinfunction "1_1") (pintype "passive"))
      (node (ref "J3") (pin "5") (pinfunction "5_5") (pintype "passive"))
      (node (ref "R77") (pin "1") (pinfunction "1_1") (pintype "passive"))
      (node (ref "U1") (pin "29") (pinfunction "PC6(/RESET)_29") (pintype "bidirectional"))
    )
    (net (code "19") (name "/ROTA") (class "Default")
      (node (ref "C23") (pin "2") (pinfunction "2_2") (pintype "passive"))
      (node (ref "R53") (pin "1") (pinfunction "1_1") (pintype "passive"))
      (node (ref "S1") (pin "A") (pinfunction "A_A") (pintype "bidirectional"))
      (node (ref "U3") (pin "5") (pinfunction "I_5") (pintype "input"))
    )
    (net (code "20") (name "/ROTA_FILT") (class "Default")
      (node (ref "U1") (pin "2") (pinfunction "PD4(XCK/T0)_2") (pintype "bidirectional"))
      (node (ref "U3") (pin "4") (pinfunction "O_4") (pintype "output"))
    )
    (net (code "21") (name "/ROTB") (class "Default")
      (node (ref "C22") (pin "2") (pinfunction "2_2") (pintype "passive"))
      (node (ref "R52") (pin "1") (pinfunction "1_1") (pintype "passive"))
      (node (ref "S1") (pin "B") (pinfunction "B_B") (pintype "bidirectional"))
      (node (ref "U3") (pin "11") (pinfunction "I_11") (pintype "input"))
    )
    (net (code "22") (name "/ROTB_FILT") (class "Default")
      (node (ref "U1") (pin "1") (pinfunction "PD3(INT1)_1") (pintype "bidirectional"))
      (node (ref "U3") (pin "8") (pinfunction "O_8") (pintype "output"))
    )
    (net (code "23") (name "/ROTPUSH") (class "Default")
      (node (ref "C24") (pin "2") (pinfunction "2_2") (pintype "passive"))
      (node (ref "R54") (pin "1") (pinfunction "1_1") (pintype "passive"))
      (node (ref "S1") (pin "SW+") (pinfunction "SW+_SW+") (pintype "bidirectional"))
      (node (ref "U3") (pin "1") (pinfunction "I_1") (pintype "input"))
    )
    (net (code "24") (name "/RPUSH_FILT") (class "Default")
      (node (ref "U1") (pin "26") (pinfunction "PC3(ADC3)_26") (pintype "bidirectional"))
      (node (ref "U3") (pin "12") (pinfunction "O_12") (pintype "output"))
    )
    (net (code "25") (name "/RST") (class "Default")
      (node (ref "J6") (pin "5") (pinfunction "RST_5") (pintype "bidirectional"))
      (node (ref "R21") (pin "2") (pinfunction "2_2") (pintype "passive"))
    )
    (net (code "26") (name "/RX-I") (class "Default")
      (node (ref "J4") (pin "P$3") (pinfunction "RXI_P$3") (pintype "bidirectional"))
      (node (ref "U1") (pin "30") (pinfunction "PD0(RXD)_30") (pintype "bidirectional"))
    )
    (net (code "27") (name "/SCK") (class "Default")
      (node (ref "J3") (pin "3") (pinfunction "3_3") (pintype "passive"))
      (node (ref "R14") (pin "1") (pinfunction "1_1") (pintype "passive"))
      (node (ref "U1") (pin "17") (pinfunction "PB5(SCK)_17") (pintype "bidirectional"))
    )
    (net (code "28") (name "/SCL") (class "Default")
      (node (ref "L5") (pin "2") (pinfunction "2_2") (pintype "passive"))
      (node (ref "R57") (pin "1") (pinfunction "1_1") (pintype "passive"))
      (node (ref "TP7") (pin "1") (pinfunction "1_1") (pintype "passive"))
      (node (ref "U1") (pin "28") (pinfunction "PC5(ADC5/SCL)_28") (pintype "bidirectional"))
    )
    (net (code "29") (name "/SDA") (class "Default")
      (node (ref "L6") (pin "2") (pinfunction "2_2") (pintype "passive"))
      (node (ref "R58") (pin "1") (pinfunction "1_1") (pintype "passive"))
      (node (ref "TP6") (pin "1") (pinfunction "1_1") (pintype "passive"))
      (node (ref "U1") (pin "27") (pinfunction "PC4(ADC4/SDA)_27") (pintype "bidirectional"))
    )
    (net (code "30") (name "/SPARE") (class "Default")
      (node (ref "C9") (pin "1") (pinfunction "1_1") (pintype "passive"))
      (node (ref "R18") (pin "2") (pinfunction "2_2") (pintype "passive"))
      (node (ref "R99") (pin "2") (pinfunction "2_2") (pintype "passive"))
      (node (ref "U1") (pin "23") (pinfunction "PC0(ADC0)_23") (pintype "bidirectional"))
      (node (ref "U6") (pin "1") (pinfunction "I_1") (pintype "input"))
    )
    (net (code "31") (name "/SS") (class "Default")
      (node (ref "R29") (pin "1") (pinfunction "1_1") (pintype "passive"))
      (node (ref "U1") (pin "14") (pinfunction "PB2(SS/OC1B)_14") (pintype "bidirectional"))
    )
    (net (code "32") (name "/TEST") (class "Default")
      (node (ref "Q1") (pin "1") (pinfunction "G_1") (pintype "passive"))
      (node (ref "R27") (pin "2") (pinfunction "2_2") (pintype "passive"))
      (node (ref "R34") (pin "2") (pinfunction "2_2") (pintype "passive"))
      (node (ref "TP13") (pin "1") (pinfunction "1_1") (pintype "passive"))
    )
    (net (code "33") (name "/TX-O") (class "Default")
      (node (ref "J4") (pin "P$2") (pinfunction "TXO_P$2") (pintype "bidirectional"))
      (node (ref "U1") (pin "31") (pinfunction "PD1(TXD)_31") (pintype "bidirectional"))
    )
    (net (code "34") (name "/VOSEN") (class "Default")
      (node (ref "C13") (pin "2") (pinfunction "2_2") (pintype "passive"))
      (node (ref "D2") (pin "3") (pinfunction "AC_3") (pintype "passive"))
      (node (ref "R36") (pin "1") (pinfunction "1_1") (pintype "passive"))
      (node (ref "R37") (pin "2") (pinfunction "2_2") (pintype "passive"))
      (node (ref "TP3") (pin "1") (pinfunction "1_1") (pintype "passive"))
      (node (ref "U1") (pin "19") (pinfunction "ADC6_19") (pintype "bidirectional"))
    )
    (net (code "35") (name "/VOUT") (class "Default")
      (node (ref "D8") (pin "C") (pinfunction "K_C") (pintype "bidirectional"))
      (node (ref "J2") (pin "1") (pinfunction "1_1") (pintype "passive"))
      (node (ref "K1") (pin "4") (pinfunction "S_4") (pintype "passive"))
      (node (ref "K1") (pin "6") (pinfunction "P_6") (pintype "passive"))
      (node (ref "K1") (pin "7") (pinfunction "O_7") (pintype "passive"))
      (node (ref "R1") (pin "2") (pinfunction "2_2") (pintype "passive"))
      (node (ref "R12") (pin "2") (pinfunction "2_2") (pintype "passive"))
      (node (ref "R37") (pin "1") (pinfunction "1_1") (pintype "passive"))
      (node (ref "TP11") (pin "1") (pinfunction "1_1") (pintype "passive"))
    )
    (net (code "36") (name "/VO_TPS") (class "Default")
      (node (ref "C19") (pin "2") (pinfunction "2_2") (pintype "passive"))
      (node (ref "C34") (pin "2") (pinfunction "2_2") (pintype "passive"))
      (node (ref "C39") (pin "1") (pinfunction "1_1") (pintype "passive"))
      (node (ref "C40") (pin "1") (pinfunction "1_1") (pintype "passive"))
      (node (ref "C41") (pin "1") (pinfunction "1_1") (pintype "passive"))
      (node (ref "C42") (pin "1") (pinfunction "1_1") (pintype "passive"))
      (node (ref "C43") (pin "1") (pinfunction "1_1") (pintype "passive"))
      (node (ref "L2") (pin "2") (pinfunction "2_2") (pintype "passive"))
      (node (ref "R11") (pin "2") (pinfunction "2_2") (pintype "passive"))
      (node (ref "R12") (pin "1") (pinfunction "1_1") (pintype "passive"))
      (node (ref "TP14") (pin "1") (pinfunction "1_1") (pintype "passive"))
      (node (ref "U4") (pin "5") (pinfunction "RS+_5") (pintype "power_in"))
    )
    (net (code "37") (name "/VRELAY") (class "Default")
      (node (ref "D3") (pin "3") (pinfunction "AC_3") (pintype "passive"))
      (node (ref "K1") (pin "8") (pinfunction "-_8") (pintype "passive"))
      (node (ref "Q3") (pin "3") (pinfunction "D_3") (pintype "passive"))
      (node (ref "TP8") (pin "1") (pinfunction "1_1") (pintype "passive"))
    )
    (net (code "38") (name "5VMCU") (class "Default")
      (node (ref "C1") (pin "2") (pinfunction "2_2") (pintype "passive"))
      (node (ref "C12") (pin "2") (pinfunction "2_2") (pintype "passive"))
      (node (ref "C15") (pin "2") (pinfunction "2_2") (pintype "passive"))
      (node (ref "C2") (pin "2") (pinfunction "2_2") (pintype "passive"))
      (node (ref "C20") (pin "2") (pinfunction "2_2") (pintype "passive"))
      (node (ref "C25") (pin "2") (pinfunction "2_2") (pintype "passive"))
      (node (ref "C26") (pin "1") (pinfunction "1_1") (pintype "passive"))
      (node (ref "C31") (pin "2") (pinfunction "2_2") (pintype "passive"))
      (node (ref "C4") (pin "1") (pinfunction "1_1") (pintype "passive"))
      (node (ref "C44") (pin "2") (pinfunction "2_2") (pintype "passive"))
      (node (ref "C45") (pin "2") (pinfunction "2_2") (pintype "passive"))
      (node (ref "C46") (pin "2") (pinfunction "2_2") (pintype "passive"))
      (node (ref "C5") (pin "2") (pinfunction "2_2") (pintype "passive"))
      (node (ref "C50") (pin "2") (pinfunction "2_2") (pintype "passive"))
      (node (ref "C51") (pin "2") (pinfunction "2_2") (pintype "passive"))
      (node (ref "C52") (pin "1") (pinfunction "1_1") (pintype "passive"))
      (node (ref "C53") (pin "2") (pinfunction "2_2") (pintype "passive"))
      (node (ref "D2") (pin "2") (pinfunction "C_2") (pintype "passive"))
      (node (ref "D3") (pin "2") (pinfunction "C_2") (pintype "passive"))
      (node (ref "J3") (pin "2") (pinfunction "2_2") (pintype "passive"))
      (node (ref "J4") (pin "P$4") (pinfunction "VCC_P$4") (pintype "bidirectional"))
      (node (ref "J6") (pin "2") (pinfunction "VCC_2") (pintype "bidirectional"))
      (node (ref "K1") (pin "1") (pinfunction "+_1") (pintype "passive"))
      (node (ref "L1") (pin "2") (pinfunction "2_2") (pintype "passive"))
      (node (ref "R13") (pin "2") (pinfunction "2_2") (pintype "passive"))
      (node (ref "R15") (pin "1") (pinfunction "1_1") (pintype "passive"))
      (node (ref "R19") (pin "2") (pinfunction "2_2") (pintype "passive"))
      (node (ref "R35") (pin "1") (pinfunction "1_1") (pintype "passive"))
      (node (ref "R38") (pin "1") (pinfunction "1_1") (pintype "passive"))
      (node (ref "R40") (pin "1") (pinfunction "1_1") (pintype "passive"))
      (node (ref "R52") (pin "2") (pinfunction "2_2") (pintype "passive"))
      (node (ref "R53") (pin "2") (pinfunction "2_2") (pintype "passive"))
      (node (ref "R54") (pin "2") (pinfunction "2_2") (pintype "passive"))
      (node (ref "R57") (pin "2") (pinfunction "2_2") (pintype "passive"))
      (node (ref "R58") (pin "2") (pinfunction "2_2") (pintype "passive"))
      (node (ref "R66") (pin "1") (pinfunction "1_1") (pintype "passive"))
      (node (ref "R77") (pin "2") (pinfunction "2_2") (pintype "passive"))
      (node (ref "U1") (pin "18") (pinfunction "AVCC_18") (pintype "bidirectional"))
      (node (ref "U1") (pin "4") (pinfunction "VCC_4") (pintype "bidirectional"))
      (node (ref "U1") (pin "6") (pinfunction "VCC_6") (pintype "bidirectional"))
      (node (ref "U3") (pin "14") (pinfunction "VCC_14") (pintype "power_in"))
      (node (ref "U6") (pin "14") (pinfunction "VCC_14") (pintype "power_in"))
      (node (ref "U7") (pin "1") (pinfunction "VCC_1") (pintype "bidirectional"))
    )
    (net (code "39") (name "GND") (class "Default")
      (node (ref "C1") (pin "1") (pinfunction "1_1") (pintype "passive"))
      (node (ref "C10") (pin "1") (pinfunction "1_1") (pintype "passive"))
      (node (ref "C11") (pin "1") (pinfunction "1_1") (pintype "passive"))
      (node (ref "C12") (pin "1") (pinfunction "1_1") (pintype "passive"))
      (node (ref "C13") (pin "1") (pinfunction "1_1") (pintype "passive"))
      (node (ref "C14") (pin "1") (pinfunction "1_1") (pintype "passive"))
      (node (ref "C15") (pin "1") (pinfunction "1_1") (pintype "passive"))
      (node (ref "C16") (pin "1") (pinfunction "1_1") (pintype "passive"))
      (node (ref "C17") (pin "2") (pinfunction "2_2") (pintype "passive"))
      (node (ref "C18") (pin "2") (pinfunction "2_2") (pintype "passive"))
      (node (ref "C2") (pin "1") (pinfunction "1_1") (pintype "passive"))
      (node (ref "C20") (pin "1") (pinfunction "1_1") (pintype "passive"))
      (node (ref "C21") (pin "2") (pinfunction "2_2") (pintype "passive"))
      (node (ref "C22") (pin "1") (pinfunction "1_1") (pintype "passive"))
      (node (ref "C23") (pin "1") (pinfunction "1_1") (pintype "passive"))
      (node (ref "C24") (pin "1") (pinfunction "1_1") (pintype "passive"))
      (node (ref "C25") (pin "1") (pinfunction "1_1") (pintype "passive"))
      (node (ref "C26") (pin "2") (pinfunction "2_2") (pintype "passive"))
      (node (ref "C27") (pin "1") (pinfunction "1_1") (pintype "passive"))
      (node (ref "C28") (pin "1") (pinfunction "1_1") (pintype "passive"))
      (node (ref "C30") (pin "1") (pinfunction "1_1") (pintype "passive"))
      (node (ref "C31") (pin "1") (pinfunction "1_1") (pintype "passive"))
      (node (ref "C32") (pin "1") (pinfunction "1_1") (pintype "passive"))
      (node (ref "C34") (pin "1") (pinfunction "1_1") (pintype "passive"))
      (node (ref "C35") (pin "2") (pinfunction "2_2") (pintype "passive"))
      (node (ref "C36") (pin "1") (pinfunction "1_1") (pintype "passive"))
      (node (ref "C38") (pin "1") (pinfunction "1_1") (pintype "passive"))
      (node (ref "C39") (pin "2") (pinfunction "2_2") (pintype "passive"))
      (node (ref "C4") (pin "2") (pinfunction "2_2") (pintype "passive"))
      (node (ref "C40") (pin "2") (pinfunction "2_2") (pintype "passive"))
      (node (ref "C41") (pin "2") (pinfunction "2_2") (pintype "passive"))
      (node (ref "C42") (pin "2") (pinfunction "2_2") (pintype "passive"))
      (node (ref "C44") (pin "1") (pinfunction "1_1") (pintype "passive"))
      (node (ref "C45") (pin "1") (pinfunction "1_1") (pintype "passive"))
      (node (ref "C46") (pin "1") (pinfunction "1_1") (pintype "passive"))
      (node (ref "C47") (pin "1") (pinfunction "1_1") (pintype "passive"))
      (node (ref "C48") (pin "1") (pinfunction "1_1") (pintype "passive"))
      (node (ref "C49") (pin "1") (pinfunction "1_1") (pintype "passive"))
      (node (ref "C50") (pin "1") (pinfunction "1_1") (pintype "passive"))
      (node (ref "C51") (pin "1") (pinfunction "1_1") (pintype "passive"))
      (node (ref "C52") (pin "2") (pinfunction "2_2") (pintype "passive"))
      (node (ref "C53") (pin "1") (pinfunction "1_1") (pintype "passive"))
      (node (ref "C54") (pin "1") (pinfunction "1_1") (pintype "passive"))
      (node (ref "C6") (pin "2") (pinfunction "2_2") (pintype "passive"))
      (node (ref "C7") (pin "1") (pinfunction "1_1") (pintype "passive"))
      (node (ref "C8") (pin "1") (pinfunction "1_1") (pintype "passive"))
      (node (ref "C9") (pin "2") (pinfunction "2_2") (pintype "passive"))
      (node (ref "D1") (pin "+") (pinfunction "A_+") (pintype "bidirectional"))
      (node (ref "D2") (pin "1") (pinfunction "A_1") (pintype "passive"))
      (node (ref "D6") (pin "1") (pinfunction "A_1") (pintype "bidirectional"))
      (node (ref "D8") (pin "A") (pinfunction "A_A") (pintype "bidirectional"))
      (node (ref "J1") (pin "1") (pinfunction "1_1") (pintype "passive"))
      (node (ref "J2") (pin "2") (pinfunction "2_2") (pintype "passive"))
      (node (ref "J3") (pin "6") (pinfunction "6_6") (pintype "passive"))
      (node (ref "J4") (pin "P$5") (pinfunction "CTS_P$5") (pintype "bidirectional"))
      (node (ref "J4") (pin "P$6") (pinfunction "GND_P$6") (pintype "bidirectional"))
      (node (ref "J6") (pin "1") (pinfunction "GND_1") (pintype "bidirectional"))
      (node (ref "K1") (pin "2") (pinfunction "O_2") (pintype "passive"))
      (node (ref "K1") (pin "3") (pinfunction "P_3") (pintype "passive"))
      (node (ref "K1") (pin "5") (pinfunction "S_5") (pintype "passive"))
      (node (ref "OP1") (pin "3") (pinfunction "EMIT_3") (pintype "passive"))
      (node (ref "Q1") (pin "2") (pinfunction "S_2") (pintype "passive"))
      (node (ref "Q2") (pin "2") (pinfunction "S_2") (pintype "passive"))
      (node (ref "Q3") (pin "2") (pinfunction "S_2") (pintype "passive"))
      (node (ref "Q9") (pin "2") (pinfunction "S_2") (pintype "passive"))
      (node (ref "R16") (pin "2") (pinfunction "2_2") (pintype "passive"))
      (node (ref "R18") (pin "1") (pinfunction "1_1") (pintype "passive"))
      (node (ref "R22") (pin "2") (pinfunction "2_2") (pintype "passive"))
      (node (ref "R32") (pin "2") (pinfunction "2_2") (pintype "passive"))
      (node (ref "R34") (pin "1") (pinfunction "1_1") (pintype "passive"))
      (node (ref "R36") (pin "2") (pinfunction "2_2") (pintype "passive"))
      (node (ref "R43") (pin "1") (pinfunction "1_1") (pintype "passive"))
      (node (ref "R44") (pin "1") (pinfunction "1_1") (pintype "passive"))
      (node (ref "S1") (pin "C") (pinfunction "C_C") (pintype "bidirectional"))
      (node (ref "S1") (pin "SW-") (pinfunction "SW-_SW-") (pintype "bidirectional"))
      (node (ref "S2") (pin "2") (pinfunction "2_2") (pintype "passive"))
      (node (ref "TP1") (pin "1") (pinfunction "1_1") (pintype "passive"))
      (node (ref "TP12") (pin "1") (pinfunction "1_1") (pintype "passive"))
      (node (ref "U1") (pin "21") (pinfunction "GND_21") (pintype "bidirectional"))
      (node (ref "U1") (pin "3") (pinfunction "GND_3") (pintype "bidirectional"))
      (node (ref "U1") (pin "5") (pinfunction "AGND_5") (pintype "bidirectional"))
      (node (ref "U2") (pin "2") (pinfunction "GND_2") (pintype "bidirectional"))
      (node (ref "U3") (pin "7") (pinfunction "GND_7") (pintype "power_in"))
      (node (ref "U4") (pin "1") (pinfunction "GND_1") (pintype "passive"))
      (node (ref "U4") (pin "2") (pinfunction "GND_2_2") (pintype "passive"))
      (node (ref "U5") (pin "3") (pinfunction "GND_3") (pintype "bidirectional"))
      (node (ref "U6") (pin "7") (pinfunction "GND_7") (pintype "power_in"))
      (node (ref "U7") (pin "10") (pinfunction "A1_10") (pintype "bidirectional"))
      (node (ref "U7") (pin "16") (pinfunction "GND_16") (pintype "bidirectional"))
      (node (ref "U7") (pin "7") (pinfunction "A2_7") (pintype "bidirectional"))
      (node (ref "U7") (pin "8") (pinfunction "~{G}_8") (pintype "bidirectional"))
      (node (ref "U7") (pin "9") (pinfunction "A0_9") (pintype "bidirectional"))
      (node (ref "U8") (pin "7") (pinfunction "GND_7") (pintype "bidirectional"))
      (node (ref "U8") (pin "PAD") (pinfunction "PAD_PAD") (pintype "bidirectional"))
      (node (ref "X1") (pin "2") (pinfunction "2_2") (pintype "passive"))
    )
    (net (code "40") (name "Net-(BZ1-+)") (class "Default")
      (node (ref "BZ1") (pin "1") (pinfunction "+_1") (pintype "passive"))
      (node (ref "C27") (pin "2") (pinfunction "2_2") (pintype "passive"))
      (node (ref "L7") (pin "2") (pinfunction "2_2") (pintype "passive"))
      (node (ref "R61") (pin "2") (pinfunction "2_2") (pintype "passive"))
    )
    (net (code "41") (name "Net-(BZ1--)") (class "Default")
      (node (ref "BZ1") (pin "2") (pinfunction "-_2") (pintype "passive"))
      (node (ref "Q9") (pin "3") (pinfunction "D_3") (pintype "passive"))
      (node (ref "R61") (pin "1") (pinfunction "1_1") (pintype "passive"))
    )
    (net (code "42") (name "Net-(C10-Pad2)") (class "Default")
      (node (ref "C10") (pin "2") (pinfunction "2_2") (pintype "passive"))
      (node (ref "R13") (pin "1") (pinfunction "1_1") (pintype "passive"))
      (node (ref "R65") (pin "2") (pinfunction "2_2") (pintype "passive"))
      (node (ref "S2") (pin "4") (pinfunction "4_4") (pintype "passive"))
    )
    (net (code "43") (name "Net-(C36-Pad2)") (class "Default")
      (node (ref "C36") (pin "2") (pinfunction "2_2") (pintype "passive"))
      (node (ref "J1") (pin "2") (pinfunction "2_2") (pintype "passive"))
      (node (ref "PTC1") (pin "2") (pinfunction "2_2") (pintype "passive"))
    )
    (net (code "44") (name "Net-(C37-Pad1)") (class "Default")
      (node (ref "C37") (pin "1") (pinfunction "1_1") (pintype "passive"))
      (node (ref "R44") (pin "2") (pinfunction "2_2") (pintype "passive"))
    )
    (net (code "45") (name "Net-(D1-K)") (class "Default")
      (node (ref "C3") (pin "2") (pinfunction "2_2") (pintype "passive"))
      (node (ref "D1") (pin "-") (pinfunction "K_-") (pintype "bidirectional"))
      (node (ref "L1") (pin "1") (pinfunction "1_1") (pintype "passive"))
      (node (ref "U2") (pin "6") (pinfunction "LX_6") (pintype "bidirectional"))
    )
    (net (code "46") (name "Net-(D5-A)") (class "Default")
      (node (ref "D5") (pin "1") (pinfunction "A_1") (pintype "bidirectional"))
      (node (ref "PTC1") (pin "1") (pinfunction "1_1") (pintype "passive"))
    )
    (net (code "47") (name "Net-(D6-K)") (class "Default")
      (node (ref "C29") (pin "2") (pinfunction "2_2") (pintype "passive"))
      (node (ref "D6") (pin "2") (pinfunction "K_2") (pintype "bidirectional"))
      (node (ref "L2") (pin "1") (pinfunction "1_1") (pintype "passive"))
      (node (ref "U8") (pin "8") (pinfunction "PH_8") (pintype "bidirectional"))
    )
    (net (code "48") (name "Net-(J5-Pad1)") (class "Default")
      (node (ref "J5") (pin "1") (pinfunction "1_1") (pintype "passive"))
      (node (ref "L3") (pin "1") (pinfunction "1_1") (pintype "passive"))
    )
    (net (code "49") (name "Net-(J5-Pad2)") (class "Default")
      (node (ref "J5") (pin "2") (pinfunction "2_2") (pintype "passive"))
      (node (ref "L4") (pin "1") (pinfunction "1_1") (pintype "passive"))
    )
    (net (code "50") (name "Net-(J6-DC)") (class "Default")
      (node (ref "J6") (pin "6") (pinfunction "DC_6") (pintype "bidirectional"))
      (node (ref "R24") (pin "2") (pinfunction "2_2") (pintype "passive"))
    )
    (net (code "51") (name "Net-(L3-Pad2)") (class "Default")
      (node (ref "L3") (pin "2") (pinfunction "2_2") (pintype "passive"))
      (node (ref "R26") (pin "1") (pinfunction "1_1") (pintype "passive"))
    )
    (net (code "52") (name "Net-(L4-Pad2)") (class "Default")
      (node (ref "L4") (pin "2") (pinfunction "2_2") (pintype "passive"))
      (node (ref "R22") (pin "1") (pinfunction "1_1") (pintype "passive"))
    )
    (net (code "53") (name "Net-(LED1-C)") (class "Default")
      (node (ref "LED1") (pin "K") (pinfunction "C_K") (pintype "passive"))
      (node (ref "Q2") (pin "3") (pinfunction "D_3") (pintype "passive"))
    )
    (net (code "54") (name "Net-(LED1-PadA)") (class "Default")
      (node (ref "LED1") (pin "A") (pinfunction "A_A") (pintype "passive"))
      (node (ref "R35") (pin "2") (pinfunction "2_2") (pintype "passive"))
    )
    (net (code "55") (name "Net-(LED2-C)") (class "Default")
      (node (ref "LED2") (pin "K") (pinfunction "C_K") (pintype "passive"))
      (node (ref "LED3") (pin "K") (pinfunction "C_K") (pintype "passive"))
      (node (ref "Q1") (pin "3") (pinfunction "D_3") (pintype "passive"))
    )
    (net (code "56") (name "Net-(LED2-PadA)") (class "Default")
      (node (ref "LED2") (pin "A") (pinfunction "A_A") (pintype "passive"))
      (node (ref "R38") (pin "2") (pinfunction "2_2") (pintype "passive"))
    )
    (net (code "57") (name "Net-(LED3-PadA)") (class "Default")
      (node (ref "LED3") (pin "A") (pinfunction "A_A") (pintype "passive"))
      (node (ref "R40") (pin "2") (pinfunction "2_2") (pintype "passive"))
    )
    (net (code "58") (name "Net-(OP1-C)") (class "Default")
      (node (ref "OP1") (pin "2") (pinfunction "C_2") (pintype "passive"))
      (node (ref "R26") (pin "2") (pinfunction "2_2") (pintype "passive"))
    )
    (net (code "59") (name "Net-(Q2-G)") (class "Default")
      (node (ref "Q2") (pin "1") (pinfunction "G_1") (pintype "passive"))
      (node (ref "R31") (pin "2") (pinfunction "2_2") (pintype "passive"))
    )
    (net (code "60") (name "Net-(Q3-G)") (class "Default")
      (node (ref "Q3") (pin "1") (pinfunction "G_1") (pintype "passive"))
      (node (ref "R30") (pin "2") (pinfunction "2_2") (pintype "passive"))
    )
    (net (code "61") (name "Net-(Q9-G)") (class "Default")
      (node (ref "Q9") (pin "1") (pinfunction "G_1") (pintype "passive"))
      (node (ref "R28") (pin "2") (pinfunction "2_2") (pintype "passive"))
      (node (ref "R32") (pin "1") (pinfunction "1_1") (pintype "passive"))
    )
    (net (code "62") (name "Net-(U1-PB1(OC1A))") (class "Default")
      (node (ref "R27") (pin "1") (pinfunction "1_1") (pintype "passive"))
      (node (ref "U1") (pin "13") (pinfunction "PB1(OC1A)_13") (pintype "bidirectional"))
    )
    (net (code "63") (name "Net-(U1-PB6(XTAL1{slash}TOSC1))") (class "Default")
      (node (ref "U1") (pin "7") (pinfunction "PB6(XTAL1/TOSC1)_7") (pintype "bidirectional"))
      (node (ref "X1") (pin "3") (pinfunction "3_3") (pintype "passive"))
    )
    (net (code "64") (name "Net-(U1-PB7(XTAL2{slash}TOSC2))") (class "Default")
      (node (ref "U1") (pin "8") (pinfunction "PB7(XTAL2/TOSC2)_8") (pintype "bidirectional"))
      (node (ref "X1") (pin "1") (pinfunction "1_1") (pintype "passive"))
    )
    (net (code "65") (name "Net-(U2-BST)") (class "Default")
      (node (ref "C3") (pin "1") (pinfunction "1_1") (pintype "passive"))
      (node (ref "U2") (pin "1") (pinfunction "BST_1") (pintype "bidirectional"))
    )
    (net (code "66") (name "Net-(U2-FB)") (class "Default")
      (node (ref "C5") (pin "1") (pinfunction "1_1") (pintype "passive"))
      (node (ref "R15") (pin "2") (pinfunction "2_2") (pintype "passive"))
      (node (ref "R16") (pin "1") (pinfunction "1_1") (pintype "passive"))
      (node (ref "U2") (pin "3") (pinfunction "FB_3") (pintype "bidirectional"))
    )
    (net (code "67") (name "Net-(U3A-I)") (class "Default")
      (node (ref "C49") (pin "2") (pinfunction "2_2") (pintype "passive"))
      (node (ref "R25") (pin "2") (pinfunction "2_2") (pintype "passive"))
      (node (ref "U3") (pin "13") (pinfunction "I_13") (pintype "input"))
    )
    (net (code "68") (name "Net-(U3B-O)") (class "Default")
      (node (ref "R2") (pin "1") (pinfunction "1_1") (pintype "passive"))
      (node (ref "U3") (pin "10") (pinfunction "O_10") (pintype "output"))
    )
    (net (code "69") (name "Net-(U3C-I)") (class "Default")
      (node (ref "C47") (pin "2") (pinfunction "2_2") (pintype "passive"))
      (node (ref "R2") (pin "2") (pinfunction "2_2") (pintype "passive"))
      (node (ref "U3") (pin "9") (pinfunction "I_9") (pintype "input"))
    )
    (net (code "70") (name "Net-(U3D-O)") (class "Default")
      (node (ref "R25") (pin "1") (pinfunction "1_1") (pintype "passive"))
      (node (ref "U3") (pin "2") (pinfunction "O_2") (pintype "output"))
    )
    (net (code "71") (name "Net-(U3E-I)") (class "Default")
      (node (ref "C48") (pin "2") (pinfunction "2_2") (pintype "passive"))
      (node (ref "R20") (pin "2") (pinfunction "2_2") (pintype "passive"))
      (node (ref "U3") (pin "3") (pinfunction "I_3") (pintype "input"))
    )
    (net (code "72") (name "Net-(U3F-O)") (class "Default")
      (node (ref "R20") (pin "1") (pinfunction "1_1") (pintype "passive"))
      (node (ref "U3") (pin "6") (pinfunction "O_6") (pintype "output"))
    )
    (net (code "73") (name "Net-(U4-RS-)") (class "Default")
      (node (ref "C43") (pin "2") (pinfunction "2_2") (pintype "passive"))
      (node (ref "R1") (pin "1") (pinfunction "1_1") (pintype "passive"))
      (node (ref "U4") (pin "4") (pinfunction "RS-_4") (pintype "input"))
    )
    (net (code "74") (name "Net-(U6A-O)") (class "Default")
      (node (ref "R39") (pin "1") (pinfunction "1_1") (pintype "passive"))
      (node (ref "U6") (pin "12") (pinfunction "O_12") (pintype "output"))
    )
    (net (code "75") (name "Net-(U6B-I)") (class "Default")
      (node (ref "C54") (pin "2") (pinfunction "2_2") (pintype "passive"))
      (node (ref "R39") (pin "2") (pinfunction "2_2") (pintype "passive"))
      (node (ref "U6") (pin "11") (pinfunction "I_11") (pintype "input"))
    )
    (net (code "76") (name "Net-(U6C-I)") (class "Default")
      (node (ref "C14") (pin "2") (pinfunction "2_2") (pintype "passive"))
      (node (ref "R33") (pin "2") (pinfunction "2_2") (pintype "passive"))
      (node (ref "U6") (pin "9") (pinfunction "I_9") (pintype "input"))
    )
    (net (code "77") (name "Net-(U6D-O)") (class "Default")
      (node (ref "R23") (pin "1") (pinfunction "1_1") (pintype "passive"))
      (node (ref "U6") (pin "2") (pinfunction "O_2") (pintype "output"))
    )
    (net (code "78") (name "Net-(U6E-I)") (class "Default")
      (node (ref "C11") (pin "2") (pinfunction "2_2") (pintype "passive"))
      (node (ref "R23") (pin "2") (pinfunction "2_2") (pintype "passive"))
      (node (ref "U6") (pin "3") (pinfunction "I_3") (pintype "input"))
    )
    (net (code "79") (name "Net-(U6F-O)") (class "Default")
      (node (ref "R33") (pin "1") (pinfunction "1_1") (pintype "passive"))
      (node (ref "U6") (pin "6") (pinfunction "O_6") (pintype "output"))
    )
    (net (code "80") (name "Net-(U7-DRAIN0)") (class "Default")
      (node (ref "R6") (pin "1") (pinfunction "1_1") (pintype "passive"))
      (node (ref "U7") (pin "3") (pinfunction "DRAIN0_3") (pintype "bidirectional"))
    )
    (net (code "81") (name "Net-(U7-DRAIN1)") (class "Default")
      (node (ref "R5") (pin "1") (pinfunction "1_1") (pintype "passive"))
      (node (ref "U7") (pin "4") (pinfunction "DRAIN1_4") (pintype "bidirectional"))
    )
    (net (code "82") (name "Net-(U7-DRAIN2)") (class "Default")
      (node (ref "R4") (pin "1") (pinfunction "1_1") (pintype "passive"))
      (node (ref "U7") (pin "5") (pinfunction "DRAIN2_5") (pintype "bidirectional"))
    )
    (net (code "83") (name "Net-(U7-DRAIN3)") (class "Default")
      (node (ref "R3") (pin "1") (pinfunction "1_1") (pintype "passive"))
      (node (ref "U7") (pin "6") (pinfunction "DRAIN3_6") (pintype "bidirectional"))
    )
    (net (code "84") (name "Net-(U7-DRAIN4)") (class "Default")
      (node (ref "R10") (pin "1") (pinfunction "1_1") (pintype "passive"))
      (node (ref "U7") (pin "11") (pinfunction "DRAIN4_11") (pintype "bidirectional"))
    )
    (net (code "85") (name "Net-(U7-DRAIN5)") (class "Default")
      (node (ref "R9") (pin "1") (pinfunction "1_1") (pintype "passive"))
      (node (ref "U7") (pin "12") (pinfunction "DRAIN5_12") (pintype "bidirectional"))
    )
    (net (code "86") (name "Net-(U7-DRAIN6)") (class "Default")
      (node (ref "R8") (pin "1") (pinfunction "1_1") (pintype "passive"))
      (node (ref "U7") (pin "13") (pinfunction "DRAIN6_13") (pintype "bidirectional"))
    )
    (net (code "87") (name "Net-(U7-DRAIN7)") (class "Default")
      (node (ref "R7") (pin "1") (pinfunction "1_1") (pintype "passive"))
      (node (ref "U7") (pin "14") (pinfunction "DRAIN7_14") (pintype "bidirectional"))
    )
    (net (code "88") (name "Net-(U7-SCL)") (class "Default")
      (node (ref "L5") (pin "1") (pinfunction "1_1") (pintype "passive"))
      (node (ref "U7") (pin "15") (pinfunction "SCL_15") (pintype "bidirectional"))
    )
    (net (code "89") (name "Net-(U7-SDA)") (class "Default")
      (node (ref "L6") (pin "1") (pinfunction "1_1") (pintype "passive"))
      (node (ref "U7") (pin "2") (pinfunction "SDA_2") (pintype "bidirectional"))
    )
    (net (code "90") (name "Net-(U8-BOOT)") (class "Default")
      (node (ref "C29") (pin "1") (pinfunction "1_1") (pintype "passive"))
      (node (ref "U8") (pin "1") (pinfunction "BOOT_1") (pintype "bidirectional"))
    )
    (net (code "91") (name "Net-(U8-COMP)") (class "Default")
      (node (ref "C37") (pin "2") (pinfunction "2_2") (pintype "passive"))
      (node (ref "C38") (pin "2") (pinfunction "2_2") (pintype "passive"))
      (node (ref "U8") (pin "6") (pinfunction "COMP_6") (pintype "bidirectional"))
    )
    (net (code "92") (name "Net-(U8-SS)") (class "Default")
      (node (ref "C30") (pin "2") (pinfunction "2_2") (pintype "passive"))
      (node (ref "U8") (pin "4") (pinfunction "SS_4") (pintype "bidirectional"))
    )
    (net (code "93") (name "Net-(U8-VSENSE)") (class "Default")
      (node (ref "C19") (pin "1") (pinfunction "1_1") (pintype "passive"))
      (node (ref "R10") (pin "2") (pinfunction "2_2") (pintype "passive"))
      (node (ref "R11") (pin "1") (pinfunction "1_1") (pintype "passive"))
      (node (ref "R3") (pin "2") (pinfunction "2_2") (pintype "passive"))
      (node (ref "R4") (pin "2") (pinfunction "2_2") (pintype "passive"))
      (node (ref "R5") (pin "2") (pinfunction "2_2") (pintype "passive"))
      (node (ref "R6") (pin "2") (pinfunction "2_2") (pintype "passive"))
      (node (ref "R7") (pin "2") (pinfunction "2_2") (pintype "passive"))
      (node (ref "R8") (pin "2") (pinfunction "2_2") (pintype "passive"))
      (node (ref "R9") (pin "2") (pinfunction "2_2") (pintype "passive"))
      (node (ref "U8") (pin "5") (pinfunction "VSENSE_5") (pintype "bidirectional"))
    )
    (net (code "94") (name "VCC") (class "Default")
      (node (ref "C17") (pin "1") (pinfunction "1_1") (pintype "passive"))
      (node (ref "C18") (pin "1") (pinfunction "1_1") (pintype "passive"))
      (node (ref "C21") (pin "1") (pinfunction "1_1") (pintype "passive"))
      (node (ref "C28") (pin "2") (pinfunction "2_2") (pintype "passive"))
      (node (ref "C35") (pin "1") (pinfunction "1_1") (pintype "passive"))
      (node (ref "C6") (pin "1") (pinfunction "1_1") (pintype "passive"))
      (node (ref "C7") (pin "2") (pinfunction "2_2") (pintype "passive"))
      (node (ref "D5") (pin "2") (pinfunction "K_2") (pintype "bidirectional"))
      (node (ref "L7") (pin "1") (pinfunction "1_1") (pintype "passive"))
      (node (ref "U2") (pin "4") (pinfunction "EN_4") (pintype "bidirectional"))
      (node (ref "U2") (pin "5") (pinfunction "VCC_5") (pintype "bidirectional"))
      (node (ref "U5") (pin "2") (pinfunction "IN_2") (pintype "bidirectional"))
      (node (ref "U8") (pin "2") (pinfunction "VIN_2") (pintype "bidirectional"))
    )
    (net (code "95") (name "VCCIO") (class "Default")
      (node (ref "C16") (pin "2") (pinfunction "2_2") (pintype "passive"))
      (node (ref "C8") (pin "2") (pinfunction "2_2") (pintype "passive"))
      (node (ref "OP1") (pin "1") (pinfunction "A_1") (pintype "passive"))
      (node (ref "TP2") (pin "1") (pinfunction "1_1") (pintype "passive"))
      (node (ref "U5") (pin "1") (pinfunction "OUT_1") (pintype "bidirectional"))
    )
    (net (code "96") (name "unconnected-(D3-A-Pad1)") (class "Default")
      (node (ref "D3") (pin "1") (pinfunction "A_1") (pintype "passive"))
    )
    (net (code "97") (name "unconnected-(S2-Pad1)") (class "Default")
      (node (ref "S2") (pin "1") (pinfunction "1_1") (pintype "passive"))
    )
    (net (code "98") (name "unconnected-(S2-Pad3)") (class "Default")
      (node (ref "S2") (pin "3") (pinfunction "3_3") (pintype "passive"))
    )
  )
)
